# Sheet1.net
KiCad netlist of a schematic drawn in Altium Designer
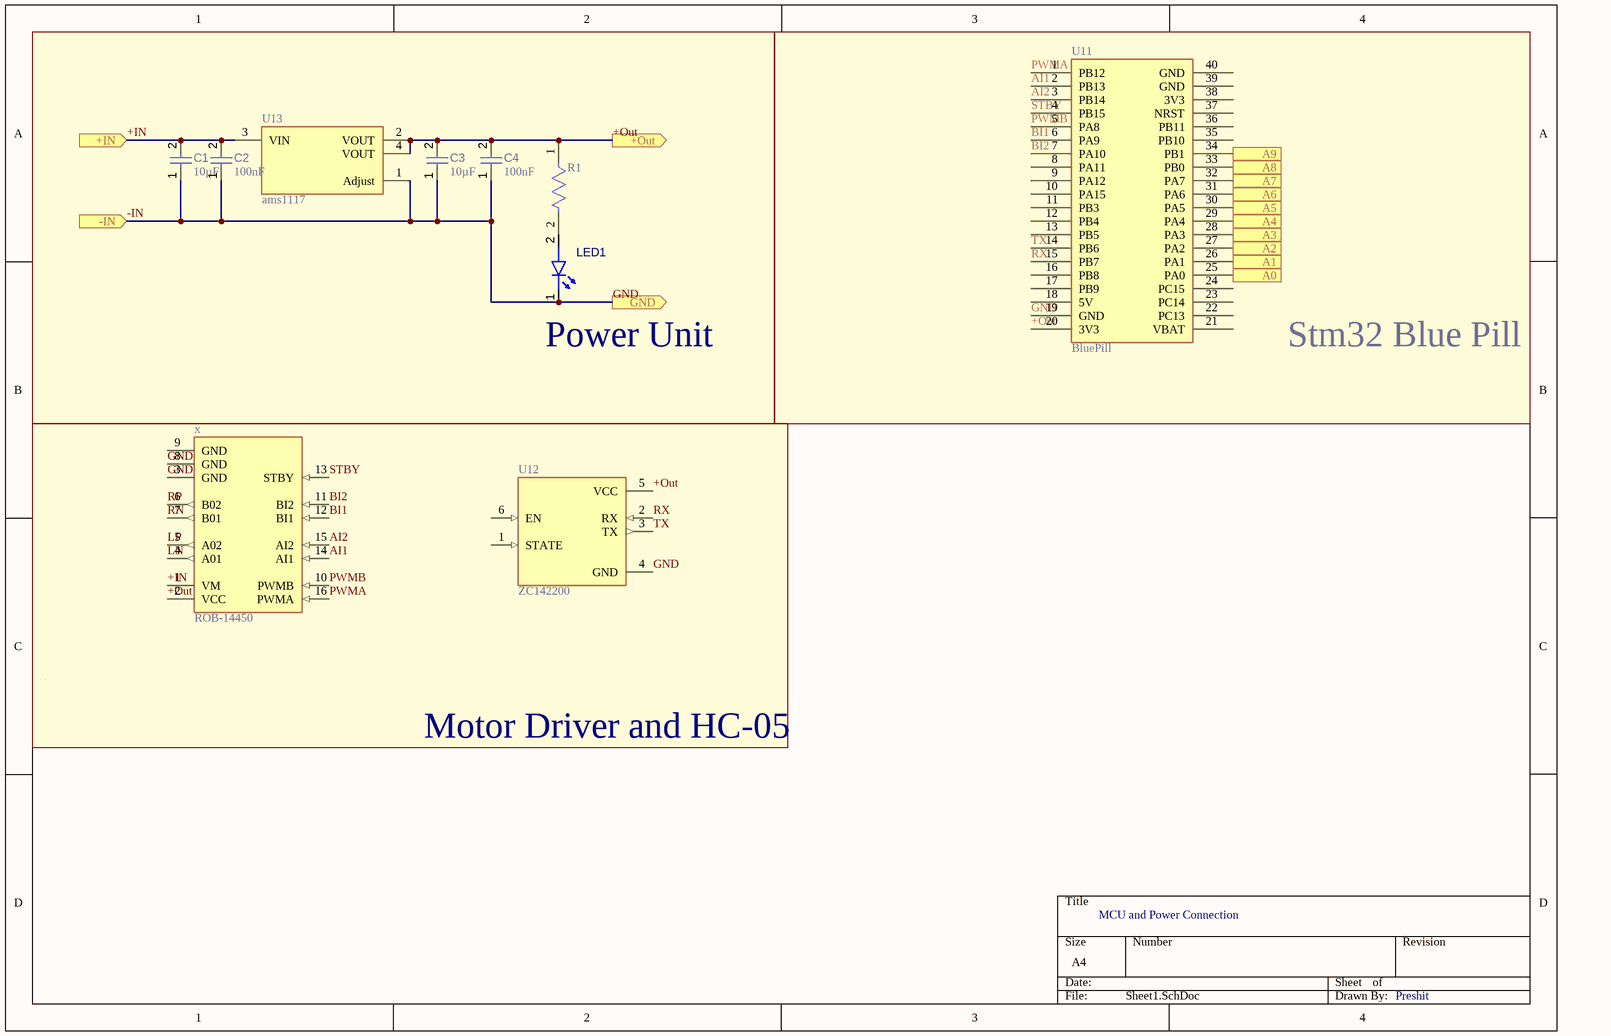
[diagram p0: Sheet1.SchDoc]

(export (version "E")
  (design (tool "Eeschema 10.0.6"))
  (components
    (comp (ref "C1")
      (value "10µF")
      (footprint "CAPC0402(1005)60_L")
      (description "Chip Capacitor, 10µF +/-40%, 6.3V, 0402, Thickness 0.6 mm")
      (fields (field (name "TOLERANCE") "10%") (field (name "Comment") "Capacitor 10µF +/-40% 6.3V 0402"))
      (libsource (lib "Preshit Sapkale") (part "CAP-NP-2"))
    )
    (comp (ref "C2")
      (value "100nF")
      (footprint "CAPC0402(1005)60_L")
      (description "Chip Capacitor, 100nF +/-20%, 10V, 0402, Thickness 0.6 mm")
      (fields (field (name "TOLERANCE") "20%") (field (name "Comment") "Capacitor 100nF +/-20% 10V 0402"))
      (libsource (lib "Preshit Sapkale") (part "CAP-NP-2"))
    )
    (comp (ref "C3")
      (value "10µF")
      (footprint "CAPC0402(1005)60_L")
      (description "Chip Capacitor, 10µF +/-40%, 6.3V, 0402, Thickness 0.6 mm")
      (fields (field (name "TOLERANCE") "10%") (field (name "Comment") "Capacitor 10µF +/-40% 6.3V 0402"))
      (libsource (lib "Preshit Sapkale") (part "CAP-NP-2"))
    )
    (comp (ref "C4")
      (value "100nF")
      (footprint "CAPC0402(1005)60_L")
      (description "Chip Capacitor, 100nF +/-20%, 10V, 0402, Thickness 0.6 mm")
      (fields (field (name "TOLERANCE") "20%") (field (name "Comment") "Capacitor 100nF +/-20% 10V 0402"))
      (libsource (lib "Preshit Sapkale") (part "CAP-NP-2"))
    )
    (comp (ref "LED1")
      (value "QBLP595-IB")
      (footprint "QTB-QBLP595_V")
      (description "Chip LED 0402, Blue, 0.02 A, 3.1 to 3.7 V, -40 to 80 degC, 2-Pin SMD, RoHS, Tape and Reel")
      (libsource (lib "Preshit Sapkale") (part "LED-KA-2"))
    )
    (comp (ref "R1")
      (value "RN73R2BTTD1001F25")
      (footprint "FP-RN73R2B-MFG")
      (description "1kΩ ±1% 0.25W, 1/4W Chip Resistor 1206 (3216 Metric) Moisture Resistant Thin Film")
      (libsource (lib "Altium Content Vault") (part "1029c3af85768c4190bb7ad29bc67b5"))
    )
    (comp (ref "U11")
      (value "BluePill")
      (footprint "Stm32 BluePill")
      (description "Designed By @Alixahedi")
      (libsource (lib "Preshit Sapkale") (part "BluePill"))
    )
    (comp (ref "U12")
      (value "ZC142200")
      (footprint "MODULE_ZC142200")
      (description "1pc HC-05 6 Pin Wireless Bluetooth RF Transceiver Module Serial For Arduino")
      (fields (field (name "MF") "YKS"))
      (libsource (lib "Preshit Sapkale") (part "ZC142200"))
    )
    (comp (ref "U13")
      (value "ams1117")
      (footprint "FP-ams1117-IPC_C")
      (description "1A LOW DROPOUT VOLTAGE REGULATOR")
      (libsource (lib "Altium Content Vault") (part "59ad430b93a2c51b3e6ee7c3b069677"))
    )
    (comp (ref "x")
      (value "ROB-14450")
      (footprint "MODULE_ROB-14450")
      (description "TB6612FNG Motor Controller/Driver Power Management Evaluation Board")
      (fields (field (name "MF") "SparkFun Electronics"))
      (libsource (lib "Preshit Sapkale") (part "ROB-14450"))
    )
  )
  (nets
    (net (code "1") (name "/+IN") (class "Default")
      (node (ref "C1") (pin "2") (pinfunction "2_2") (pintype "passive"))
      (node (ref "C2") (pin "2") (pinfunction "2_2") (pintype "passive"))
      (node (ref "U13") (pin "3") (pinfunction "VIN_3") (pintype "power_in"))
      (node (ref "x") (pin "1") (pinfunction "VM_1") (pintype "power_in"))
    )
    (net (code "2") (name "/+Out") (class "Default")
      (node (ref "C3") (pin "2") (pinfunction "2_2") (pintype "passive"))
      (node (ref "C4") (pin "2") (pinfunction "2_2") (pintype "passive"))
      (node (ref "R1") (pin "1") (pinfunction "1_1") (pintype "passive"))
      (node (ref "U11") (pin "20") (pinfunction "3V3_20") (pintype "passive"))
      (node (ref "U12") (pin "5") (pinfunction "VCC_5") (pintype "power_in"))
      (node (ref "U13") (pin "2") (pinfunction "VOUT_2") (pintype "passive"))
      (node (ref "U13") (pin "4") (pinfunction "VOUT_4") (pintype "passive"))
      (node (ref "x") (pin "2") (pinfunction "VCC_2") (pintype "power_in"))
    )
    (net (code "3") (name "/-IN") (class "Default")
      (node (ref "C1") (pin "1") (pinfunction "1_1") (pintype "passive"))
      (node (ref "C2") (pin "1") (pinfunction "1_1") (pintype "passive"))
      (node (ref "C3") (pin "1") (pinfunction "1_1") (pintype "passive"))
      (node (ref "C4") (pin "1") (pinfunction "1_1") (pintype "passive"))
      (node (ref "LED1") (pin "1") (pinfunction "K_1") (pintype "passive"))
      (node (ref "U11") (pin "19") (pinfunction "GND_19") (pintype "passive"))
      (node (ref "U12") (pin "4") (pinfunction "GND_4") (pintype "power_in"))
      (node (ref "U13") (pin "1") (pinfunction "Adjust_1") (pintype "passive"))
      (node (ref "x") (pin "3") (pinfunction "GND_3") (pintype "power_in"))
      (node (ref "x") (pin "8") (pinfunction "GND_8") (pintype "power_in"))
    )
    (net (code "4") (name "/A0") (class "Default")
      (node (ref "U11") (pin "25") (pinfunction "PA0_25") (pintype "passive"))
    )
    (net (code "5") (name "/A1") (class "Default")
      (node (ref "U11") (pin "26") (pinfunction "PA1_26") (pintype "passive"))
    )
    (net (code "6") (name "/A2") (class "Default")
      (node (ref "U11") (pin "27") (pinfunction "PA2_27") (pintype "passive"))
    )
    (net (code "7") (name "/A3") (class "Default")
      (node (ref "U11") (pin "28") (pinfunction "PA3_28") (pintype "passive"))
    )
    (net (code "8") (name "/A4") (class "Default")
      (node (ref "U11") (pin "29") (pinfunction "PA4_29") (pintype "passive"))
    )
    (net (code "9") (name "/A5") (class "Default")
      (node (ref "U11") (pin "30") (pinfunction "PA5_30") (pintype "passive"))
    )
    (net (code "10") (name "/A6") (class "Default")
      (node (ref "U11") (pin "31") (pinfunction "PA6_31") (pintype "passive"))
    )
    (net (code "11") (name "/A7") (class "Default")
      (node (ref "U11") (pin "32") (pinfunction "PA7_32") (pintype "passive"))
    )
    (net (code "12") (name "/A8") (class "Default")
      (node (ref "U11") (pin "33") (pinfunction "PB0_33") (pintype "passive"))
    )
    (net (code "13") (name "/A9") (class "Default")
      (node (ref "U11") (pin "34") (pinfunction "PB1_34") (pintype "passive"))
    )
    (net (code "14") (name "/AI1") (class "Default")
      (node (ref "U11") (pin "2") (pinfunction "PB13_2") (pintype "passive"))
      (node (ref "x") (pin "14") (pinfunction "AI1_14") (pintype "input"))
    )
    (net (code "15") (name "/AI2") (class "Default")
      (node (ref "U11") (pin "3") (pinfunction "PB14_3") (pintype "passive"))
      (node (ref "x") (pin "15") (pinfunction "AI2_15") (pintype "input"))
    )
    (net (code "16") (name "/BI1") (class "Default")
      (node (ref "U11") (pin "6") (pinfunction "PA9_6") (pintype "passive"))
      (node (ref "x") (pin "12") (pinfunction "BI1_12") (pintype "input"))
    )
    (net (code "17") (name "/BI2") (class "Default")
      (node (ref "U11") (pin "7") (pinfunction "PA10_7") (pintype "passive"))
      (node (ref "x") (pin "11") (pinfunction "BI2_11") (pintype "input"))
    )
    (net (code "18") (name "/LN") (class "Default")
      (node (ref "x") (pin "4") (pinfunction "A01_4") (pintype "output"))
    )
    (net (code "19") (name "/LP") (class "Default")
      (node (ref "x") (pin "5") (pinfunction "A02_5") (pintype "output"))
    )
    (net (code "20") (name "/PWMA") (class "Default")
      (node (ref "U11") (pin "1") (pinfunction "PB12_1") (pintype "passive"))
      (node (ref "x") (pin "16") (pinfunction "PWMA_16") (pintype "input"))
    )
    (net (code "21") (name "/PWMB") (class "Default")
      (node (ref "U11") (pin "5") (pinfunction "PA8_5") (pintype "passive"))
      (node (ref "x") (pin "10") (pinfunction "PWMB_10") (pintype "input"))
    )
    (net (code "22") (name "/RN") (class "Default")
      (node (ref "x") (pin "7") (pinfunction "B01_7") (pintype "output"))
    )
    (net (code "23") (name "/RP") (class "Default")
      (node (ref "x") (pin "6") (pinfunction "B02_6") (pintype "output"))
    )
    (net (code "24") (name "/RX") (class "Default")
      (node (ref "U11") (pin "15") (pinfunction "PB7_15") (pintype "passive"))
      (node (ref "U12") (pin "2") (pinfunction "RX_2") (pintype "input"))
    )
    (net (code "25") (name "/STBY") (class "Default")
      (node (ref "U11") (pin "4") (pinfunction "PB15_4") (pintype "passive"))
      (node (ref "x") (pin "13") (pinfunction "STBY_13") (pintype "input"))
    )
    (net (code "26") (name "/TX") (class "Default")
      (node (ref "U11") (pin "14") (pinfunction "PB6_14") (pintype "passive"))
      (node (ref "U12") (pin "3") (pinfunction "TX_3") (pintype "output"))
    )
    (net (code "27") (name "Net-(LED1-A)") (class "Default")
      (node (ref "LED1") (pin "2") (pinfunction "A_2") (pintype "passive"))
      (node (ref "R1") (pin "2") (pinfunction "2_2") (pintype "passive"))
    )
    (net (code "28") (name "unconnected-(U11-3V3-Pad38)") (class "Default")
      (node (ref "U11") (pin "38") (pinfunction "3V3_38") (pintype "passive"))
    )
    (net (code "29") (name "unconnected-(U11-5V-Pad18)") (class "Default")
      (node (ref "U11") (pin "18") (pinfunction "5V_18") (pintype "passive"))
    )
    (net (code "30") (name "unconnected-(U11-GND-Pad39)") (class "Default")
      (node (ref "U11") (pin "39") (pinfunction "GND_39") (pintype "passive"))
    )
    (net (code "31") (name "unconnected-(U11-GND-Pad40)") (class "Default")
      (node (ref "U11") (pin "40") (pinfunction "GND_40") (pintype "passive"))
    )
    (net (code "32") (name "unconnected-(U11-NRST-Pad37)") (class "Default")
      (node (ref "U11") (pin "37") (pinfunction "NRST_37") (pintype "passive"))
    )
    (net (code "33") (name "unconnected-(U11-PA11-Pad8)") (class "Default")
      (node (ref "U11") (pin "8") (pinfunction "PA11_8") (pintype "passive"))
    )
    (net (code "34") (name "unconnected-(U11-PA12-Pad9)") (class "Default")
      (node (ref "U11") (pin "9") (pinfunction "PA12_9") (pintype "passive"))
    )
    (net (code "35") (name "unconnected-(U11-PA15-Pad10)") (class "Default")
      (node (ref "U11") (pin "10") (pinfunction "PA15_10") (pintype "passive"))
    )
    (net (code "36") (name "unconnected-(U11-PB3-Pad11)") (class "Default")
      (node (ref "U11") (pin "11") (pinfunction "PB3_11") (pintype "passive"))
    )
    (net (code "37") (name "unconnected-(U11-PB4-Pad12)") (class "Default")
      (node (ref "U11") (pin "12") (pinfunction "PB4_12") (pintype "passive"))
    )
    (net (code "38") (name "unconnected-(U11-PB5-Pad13)") (class "Default")
      (node (ref "U11") (pin "13") (pinfunction "PB5_13") (pintype "passive"))
    )
    (net (code "39") (name "unconnected-(U11-PB8-Pad16)") (class "Default")
      (node (ref "U11") (pin "16") (pinfunction "PB8_16") (pintype "passive"))
    )
    (net (code "40") (name "unconnected-(U11-PB9-Pad17)") (class "Default")
      (node (ref "U11") (pin "17") (pinfunction "PB9_17") (pintype "passive"))
    )
    (net (code "41") (name "unconnected-(U11-PB10-Pad35)") (class "Default")
      (node (ref "U11") (pin "35") (pinfunction "PB10_35") (pintype "passive"))
    )
    (net (code "42") (name "unconnected-(U11-PB11-Pad36)") (class "Default")
      (node (ref "U11") (pin "36") (pinfunction "PB11_36") (pintype "passive"))
    )
    (net (code "43") (name "unconnected-(U11-PC13-Pad22)") (class "Default")
      (node (ref "U11") (pin "22") (pinfunction "PC13_22") (pintype "passive"))
    )
    (net (code "44") (name "unconnected-(U11-PC14-Pad23)") (class "Default")
      (node (ref "U11") (pin "23") (pinfunction "PC14_23") (pintype "passive"))
    )
    (net (code "45") (name "unconnected-(U11-PC15-Pad24)") (class "Default")
      (node (ref "U11") (pin "24") (pinfunction "PC15_24") (pintype "passive"))
    )
    (net (code "46") (name "unconnected-(U11-VBAT-Pad21)") (class "Default")
      (node (ref "U11") (pin "21") (pinfunction "VBAT_21") (pintype "passive"))
    )
    (net (code "47") (name "unconnected-(U12-EN-Pad6)") (class "Default")
      (node (ref "U12") (pin "6") (pinfunction "EN_6") (pintype "input"))
    )
    (net (code "48") (name "unconnected-(U12-STATE-Pad1)") (class "Default")
      (node (ref "U12") (pin "1") (pinfunction "STATE_1") (pintype "input"))
    )
    (net (code "49") (name "unconnected-(x-GND-Pad9)") (class "Default")
      (node (ref "x") (pin "9") (pinfunction "GND_9") (pintype "power_in"))
    )
  )
)
